# pwr_ctl.net
KiCad netlist of a schematic drawn in EAGLE
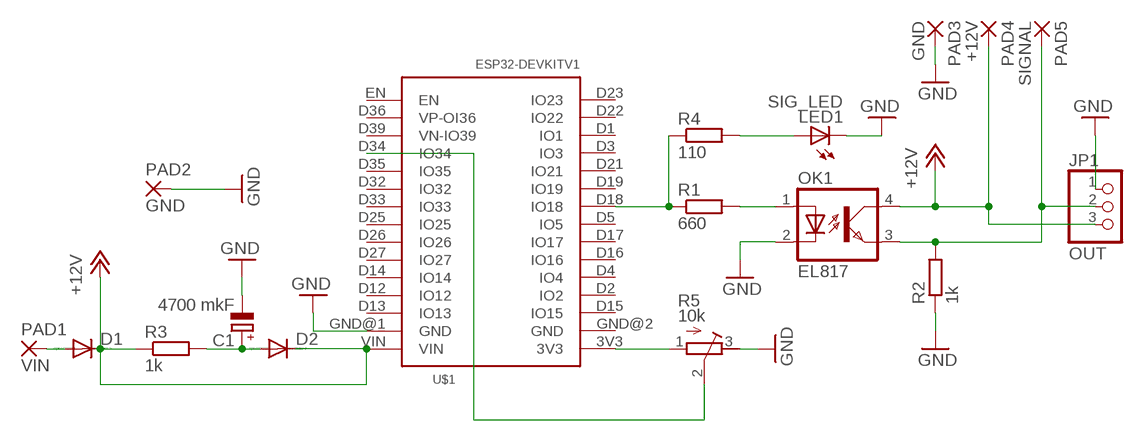
[diagram p0: schematic, sheet 1]

(export (version "E")
  (design (tool "Eeschema 10.0.6"))
  (components
    (comp (ref "C1")
      (value "4700 mkF")
      (footprint "eagle-import:E7,5-18")
      (libsource (lib "eagle-import") (part "CPOL-EUE7.5-18"))
    )
    (comp (ref "D1")
      (value "CGRM4007-G")
      (footprint "eagle-import:SOD-123_MINI-SMA")
      (libsource (lib "eagle-import") (part "CGRM400-G7"))
    )
    (comp (ref "D2")
      (value "CGRM4007-G")
      (footprint "eagle-import:SOD-123_MINI-SMA")
      (libsource (lib "eagle-import") (part "CGRM400-G7"))
    )
    (comp (ref "JP1")
      (value "OUT")
      (footprint "eagle-import:1X03")
      (libsource (lib "eagle-import") (part "PINHD-1X3"))
    )
    (comp (ref "LED1")
      (value "SIG_LED")
      (footprint "eagle-import:SML0805")
      (libsource (lib "eagle-import") (part "LEDSML0805"))
    )
    (comp (ref "OK1")
      (value "EL817")
      (footprint "eagle-import:SMD4")
      (libsource (lib "eagle-import") (part "LTV816S"))
    )
    (comp (ref "PAD1")
      (value "VIN")
      (footprint "eagle-import:SMD2,54-5,08")
      (libsource (lib "eagle-import") (part "SMD5"))
    )
    (comp (ref "PAD2")
      (value "GND")
      (footprint "eagle-import:SMD2,54-5,08")
      (libsource (lib "eagle-import") (part "SMD5"))
    )
    (comp (ref "PAD3")
      (value "GND")
      (footprint "eagle-import:SMD2,54-5,08")
      (libsource (lib "eagle-import") (part "SMD5"))
    )
    (comp (ref "PAD4")
      (value "+12V")
      (footprint "eagle-import:SMD2,54-5,08")
      (libsource (lib "eagle-import") (part "SMD5"))
    )
    (comp (ref "PAD5")
      (value "SIGNAL")
      (footprint "eagle-import:SMD2,54-5,08")
      (libsource (lib "eagle-import") (part "SMD5"))
    )
    (comp (ref "R1")
      (value "660")
      (footprint "eagle-import:R0805")
      (libsource (lib "eagle-import") (part "R-EU_R0805"))
    )
    (comp (ref "R2")
      (value "1k")
      (footprint "eagle-import:R0805")
      (libsource (lib "eagle-import") (part "R-EU_R0805"))
    )
    (comp (ref "R3")
      (value "1k")
      (footprint "eagle-import:R0805")
      (libsource (lib "eagle-import") (part "R-EU_R0805"))
    )
    (comp (ref "R4")
      (value "110")
      (footprint "eagle-import:R0805")
      (libsource (lib "eagle-import") (part "R-EU_R0805"))
    )
    (comp (ref "R5")
      (value "10k")
      (footprint "eagle-import:RTRIM3296W")
      (libsource (lib "eagle-import") (part "R-TRIMM3296W"))
    )
    (comp (ref "U$1")
      (value "ESP32DEVKITV1")
      (footprint "eagle-import:ESP32-DEVKITV1")
      (libsource (lib "eagle-import") (part "ESP32DEVKITV1"))
    )
  )
  (nets
    (net (code "1") (name "+12V") (class "Default")
      (node (ref "D1") (pin "C") (pinfunction "C_C") (pintype "passive"))
      (node (ref "D2") (pin "C") (pinfunction "C_C") (pintype "passive"))
      (node (ref "JP1") (pin "3") (pinfunction "3_3") (pintype "passive"))
      (node (ref "OK1") (pin "4") (pinfunction "COL_4") (pintype "passive"))
      (node (ref "PAD4") (pin "1") (pinfunction "P_1") (pintype "passive"))
      (node (ref "R3") (pin "1") (pinfunction "1_1") (pintype "passive"))
      (node (ref "U$1") (pin "VIN") (pinfunction "VIN_VIN") (pintype "bidirectional"))
    )
    (net (code "2") (name "GND") (class "Default")
      (node (ref "C1") (pin "-") (pinfunction "-_-") (pintype "passive"))
      (node (ref "JP1") (pin "1") (pinfunction "1_1") (pintype "passive"))
      (node (ref "LED1") (pin "C") (pinfunction "C_C") (pintype "passive"))
      (node (ref "OK1") (pin "2") (pinfunction "C_2") (pintype "passive"))
      (node (ref "PAD2") (pin "1") (pinfunction "P_1") (pintype "passive"))
      (node (ref "PAD3") (pin "1") (pinfunction "P_1") (pintype "passive"))
      (node (ref "R2") (pin "1") (pinfunction "1_1") (pintype "passive"))
      (node (ref "R5") (pin "3") (pinfunction "E_3") (pintype "passive"))
      (node (ref "U$1") (pin "GND@1") (pinfunction "GND_GND@1") (pintype "bidirectional"))
    )
    (net (code "3") (name "Net-(C1-Pad+)") (class "Default")
      (node (ref "C1") (pin "+") (pinfunction "+_+") (pintype "passive"))
      (node (ref "D2") (pin "A") (pinfunction "A_A") (pintype "passive"))
      (node (ref "R3") (pin "2") (pinfunction "2_2") (pintype "passive"))
    )
    (net (code "4") (name "Net-(LED1-PadA)") (class "Default")
      (node (ref "LED1") (pin "A") (pinfunction "A_A") (pintype "passive"))
      (node (ref "R4") (pin "2") (pinfunction "2_2") (pintype "passive"))
    )
    (net (code "5") (name "Net-(OK1-A)") (class "Default")
      (node (ref "OK1") (pin "1") (pinfunction "A_1") (pintype "passive"))
      (node (ref "R1") (pin "2") (pinfunction "2_2") (pintype "passive"))
    )
    (net (code "6") (name "Net-(OK1-EMIT)") (class "Default")
      (node (ref "JP1") (pin "2") (pinfunction "2_2") (pintype "passive"))
      (node (ref "OK1") (pin "3") (pinfunction "EMIT_3") (pintype "passive"))
      (node (ref "PAD5") (pin "1") (pinfunction "P_1") (pintype "passive"))
      (node (ref "R2") (pin "2") (pinfunction "2_2") (pintype "passive"))
    )
    (net (code "7") (name "Net-(PAD1-P)") (class "Default")
      (node (ref "D1") (pin "A") (pinfunction "A_A") (pintype "passive"))
      (node (ref "PAD1") (pin "1") (pinfunction "P_1") (pintype "passive"))
    )
    (net (code "8") (name "Net-(R5-A)") (class "Default")
      (node (ref "R5") (pin "1") (pinfunction "A_1") (pintype "passive"))
      (node (ref "U$1") (pin "3V3") (pinfunction "3V3_3V3") (pintype "bidirectional"))
    )
    (net (code "9") (name "Net-(R5-S)") (class "Default")
      (node (ref "R5") (pin "2") (pinfunction "S_2") (pintype "passive"))
      (node (ref "U$1") (pin "D34") (pinfunction "IO34_D34") (pintype "bidirectional"))
    )
    (net (code "10") (name "Net-(U$1-IO18)") (class "Default")
      (node (ref "R1") (pin "1") (pinfunction "1_1") (pintype "passive"))
      (node (ref "R4") (pin "1") (pinfunction "1_1") (pintype "passive"))
      (node (ref "U$1") (pin "D18") (pinfunction "IO18_D18") (pintype "bidirectional"))
    )
    (net (code "11") (name "unconnected-(U$1-GND-PadGND@2)") (class "Default")
      (node (ref "U$1") (pin "GND@2") (pinfunction "GND_GND@2") (pintype "bidirectional"))
    )
    (net (code "12") (name "unconnected-(U$1-IO1-PadD1)") (class "Default")
      (node (ref "U$1") (pin "D1") (pinfunction "IO1_D1") (pintype "bidirectional"))
    )
    (net (code "13") (name "unconnected-(U$1-IO2-PadD2)") (class "Default")
      (node (ref "U$1") (pin "D2") (pinfunction "IO2_D2") (pintype "bidirectional"))
    )
    (net (code "14") (name "unconnected-(U$1-IO3-PadD3)") (class "Default")
      (node (ref "U$1") (pin "D3") (pinfunction "IO3_D3") (pintype "bidirectional"))
    )
    (net (code "15") (name "unconnected-(U$1-IO4-PadD4)") (class "Default")
      (node (ref "U$1") (pin "D4") (pinfunction "IO4_D4") (pintype "bidirectional"))
    )
    (net (code "16") (name "unconnected-(U$1-IO5-PadD5)") (class "Default")
      (node (ref "U$1") (pin "D5") (pinfunction "IO5_D5") (pintype "bidirectional"))
    )
    (net (code "17") (name "unconnected-(U$1-IO12-PadD12)") (class "Default")
      (node (ref "U$1") (pin "D12") (pinfunction "IO12_D12") (pintype "bidirectional"))
    )
    (net (code "18") (name "unconnected-(U$1-IO13-PadD13)") (class "Default")
      (node (ref "U$1") (pin "D13") (pinfunction "IO13_D13") (pintype "bidirectional"))
    )
    (net (code "19") (name "unconnected-(U$1-IO14-PadD14)") (class "Default")
      (node (ref "U$1") (pin "D14") (pinfunction "IO14_D14") (pintype "bidirectional"))
    )
    (net (code "20") (name "unconnected-(U$1-IO15-PadD15)") (class "Default")
      (node (ref "U$1") (pin "D15") (pinfunction "IO15_D15") (pintype "bidirectional"))
    )
    (net (code "21") (name "unconnected-(U$1-IO16-PadD16)") (class "Default")
      (node (ref "U$1") (pin "D16") (pinfunction "IO16_D16") (pintype "bidirectional"))
    )
    (net (code "22") (name "unconnected-(U$1-IO17-PadD17)") (class "Default")
      (node (ref "U$1") (pin "D17") (pinfunction "IO17_D17") (pintype "bidirectional"))
    )
    (net (code "23") (name "unconnected-(U$1-IO19-PadD19)") (class "Default")
      (node (ref "U$1") (pin "D19") (pinfunction "IO19_D19") (pintype "bidirectional"))
    )
    (net (code "24") (name "unconnected-(U$1-IO21-PadD21)") (class "Default")
      (node (ref "U$1") (pin "D21") (pinfunction "IO21_D21") (pintype "bidirectional"))
    )
    (net (code "25") (name "unconnected-(U$1-IO22-PadD22)") (class "Default")
      (node (ref "U$1") (pin "D22") (pinfunction "IO22_D22") (pintype "bidirectional"))
    )
    (net (code "26") (name "unconnected-(U$1-IO23-PadD23)") (class "Default")
      (node (ref "U$1") (pin "D23") (pinfunction "IO23_D23") (pintype "bidirectional"))
    )
    (net (code "27") (name "unconnected-(U$1-IO25-PadD25)") (class "Default")
      (node (ref "U$1") (pin "D25") (pinfunction "IO25_D25") (pintype "bidirectional"))
    )
    (net (code "28") (name "unconnected-(U$1-IO26-PadD26)") (class "Default")
      (node (ref "U$1") (pin "D26") (pinfunction "IO26_D26") (pintype "bidirectional"))
    )
    (net (code "29") (name "unconnected-(U$1-IO27-PadD27)") (class "Default")
      (node (ref "U$1") (pin "D27") (pinfunction "IO27_D27") (pintype "bidirectional"))
    )
    (net (code "30") (name "unconnected-(U$1-IO32-PadD32)") (class "Default")
      (node (ref "U$1") (pin "D32") (pinfunction "IO32_D32") (pintype "bidirectional"))
    )
    (net (code "31") (name "unconnected-(U$1-IO33-PadD33)") (class "Default")
      (node (ref "U$1") (pin "D33") (pinfunction "IO33_D33") (pintype "bidirectional"))
    )
    (net (code "32") (name "unconnected-(U$1-IO35-PadD35)") (class "Default")
      (node (ref "U$1") (pin "D35") (pinfunction "IO35_D35") (pintype "bidirectional"))
    )
    (net (code "33") (name "unconnected-(U$1-PadEN)") (class "Default")
      (node (ref "U$1") (pin "EN") (pinfunction "EN_EN") (pintype "bidirectional"))
    )
    (net (code "34") (name "unconnected-(U$1-VN-IO39-PadD39)") (class "Default")
      (node (ref "U$1") (pin "D39") (pinfunction "VN-IO39_D39") (pintype "bidirectional"))
    )
    (net (code "35") (name "unconnected-(U$1-VP-OI36-PadD36)") (class "Default")
      (node (ref "U$1") (pin "D36") (pinfunction "VP-OI36_D36") (pintype "bidirectional"))
    )
  )
)
